# CV_LEDControl.net
KiCad netlist of a schematic drawn in EAGLE
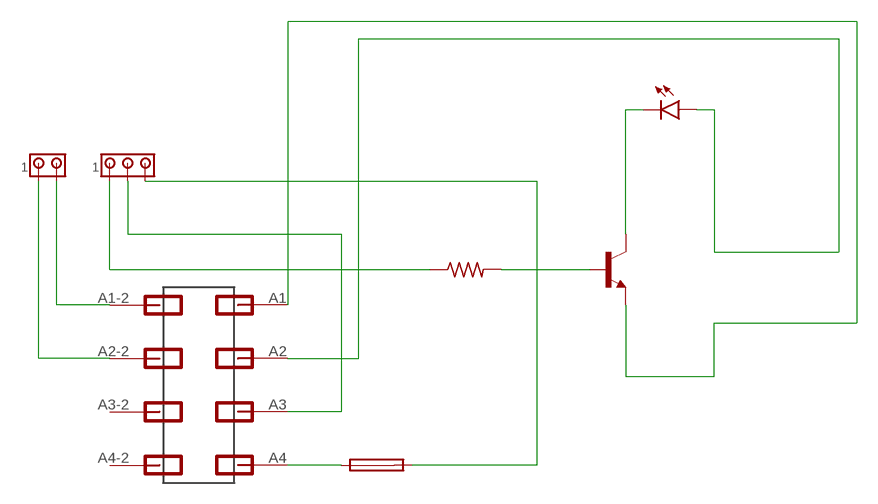
[diagram p0: schematic, sheet 1]

(export (version "E")
  (design (tool "Eeschema 10.0.6"))
  (components
    (comp (ref "E1")
      (value "WEIDMUELLER_1824440000WEIDMUELLER_1824440000_0_0")
      (footprint "eagle-import:WEIDMUELLER_1824440000_0")
      (fields (field (name "MF") "Weidmueller") (field (name "MPN") "1824440000"))
      (libsource (lib "eagle-import") (part "WEIDMUELLER_1824440000WEIDMUELLER_1824440000_0_0"))
    )
    (comp (ref "F1")
      (value "SH22,5")
      (footprint "eagle-import:SH22,5")
      (fields (field (name "MF") "SCHURTER") (field (name "MPN") "0031.8201"))
      (libsource (lib "eagle-import") (part "SH22,5"))
    )
    (comp (ref "J1")
      (value "MTA03-100")
      (footprint "eagle-import:10X03MTA")
      (fields (field (name "SPICEPREFIX") "X"))
      (libsource (lib "eagle-import") (part "MTA03-100"))
    )
    (comp (ref "J2")
      (value "MTA02-100")
      (footprint "eagle-import:10X02MTA")
      (fields (field (name "SPICEPREFIX") "B"))
      (libsource (lib "eagle-import") (part "MTA02-100"))
    )
    (comp (ref "LED1")
      (value "LED3MM")
      (footprint "eagle-import:LED3MM")
      (libsource (lib "eagle-import") (part "LED3MM"))
    )
    (comp (ref "R1")
      (value "R-US_0204/7")
      (footprint "eagle-import:0204_7")
      (libsource (lib "eagle-import") (part "R-US_0204/7"))
    )
    (comp (ref "T1")
      (value "2N2102")
      (footprint "eagle-import:TO5")
      (libsource (lib "eagle-import") (part "2N2102"))
    )
  )
  (nets
    (net (code "1") (name "Net-(E1-A1)") (class "Default")
      (node (ref "E1") (pin "A2") (pinfunction "A1_A2") (pintype "passive"))
      (node (ref "LED1") (pin "A") (pinfunction "A_A") (pintype "passive"))
    )
    (net (code "2") (name "Net-(E1-A2)") (class "Default")
      (node (ref "E1") (pin "A3") (pinfunction "A2_A3") (pintype "passive"))
      (node (ref "J1") (pin "2") (pinfunction "2_2") (pintype "passive"))
    )
    (net (code "3") (name "Net-(E1-A3)") (class "Default")
      (node (ref "E1") (pin "A4") (pinfunction "A3_A4") (pintype "passive"))
      (node (ref "F1") (pin "1") (pinfunction "1_1") (pintype "passive"))
    )
    (net (code "4") (name "Net-(E1-A4)") (class "Default")
      (node (ref "E1") (pin "A1") (pinfunction "A4_A1") (pintype "passive"))
      (node (ref "T1") (pin "1") (pinfunction "E_1") (pintype "passive"))
    )
    (net (code "5") (name "Net-(E1-A5)") (class "Default")
      (node (ref "E1") (pin "A1-2") (pinfunction "A5_A1-2") (pintype "passive"))
      (node (ref "J2") (pin "2") (pinfunction "2_2") (pintype "passive"))
    )
    (net (code "6") (name "Net-(E1-A6)") (class "Default")
      (node (ref "E1") (pin "A2-2") (pinfunction "A6_A2-2") (pintype "passive"))
      (node (ref "J2") (pin "1") (pinfunction "1_1") (pintype "passive"))
    )
    (net (code "7") (name "Net-(F1-Pad2)") (class "Default")
      (node (ref "F1") (pin "2") (pinfunction "2_2") (pintype "passive"))
      (node (ref "J1") (pin "3") (pinfunction "3_3") (pintype "passive"))
    )
    (net (code "8") (name "Net-(J1-Pad1)") (class "Default")
      (node (ref "J1") (pin "1") (pinfunction "1_1") (pintype "passive"))
      (node (ref "R1") (pin "1") (pinfunction "1_1") (pintype "passive"))
    )
    (net (code "9") (name "Net-(LED1-C)") (class "Default")
      (node (ref "LED1") (pin "K") (pinfunction "C_K") (pintype "passive"))
      (node (ref "T1") (pin "3") (pinfunction "C_3") (pintype "passive"))
    )
    (net (code "10") (name "Net-(T1-B)") (class "Default")
      (node (ref "R1") (pin "2") (pinfunction "2_2") (pintype "passive"))
      (node (ref "T1") (pin "2") (pinfunction "B_2") (pintype "passive"))
    )
    (net (code "11") (name "unconnected-(E1-A7-PadA3-2)") (class "Default")
      (node (ref "E1") (pin "A3-2") (pinfunction "A7_A3-2") (pintype "passive"))
    )
    (net (code "12") (name "unconnected-(E1-A8-PadA4-2)") (class "Default")
      (node (ref "E1") (pin "A4-2") (pinfunction "A8_A4-2") (pintype "passive"))
    )
  )
)
